# CAN_schematic.net
KiCad netlist of a schematic drawn in Altium Designer
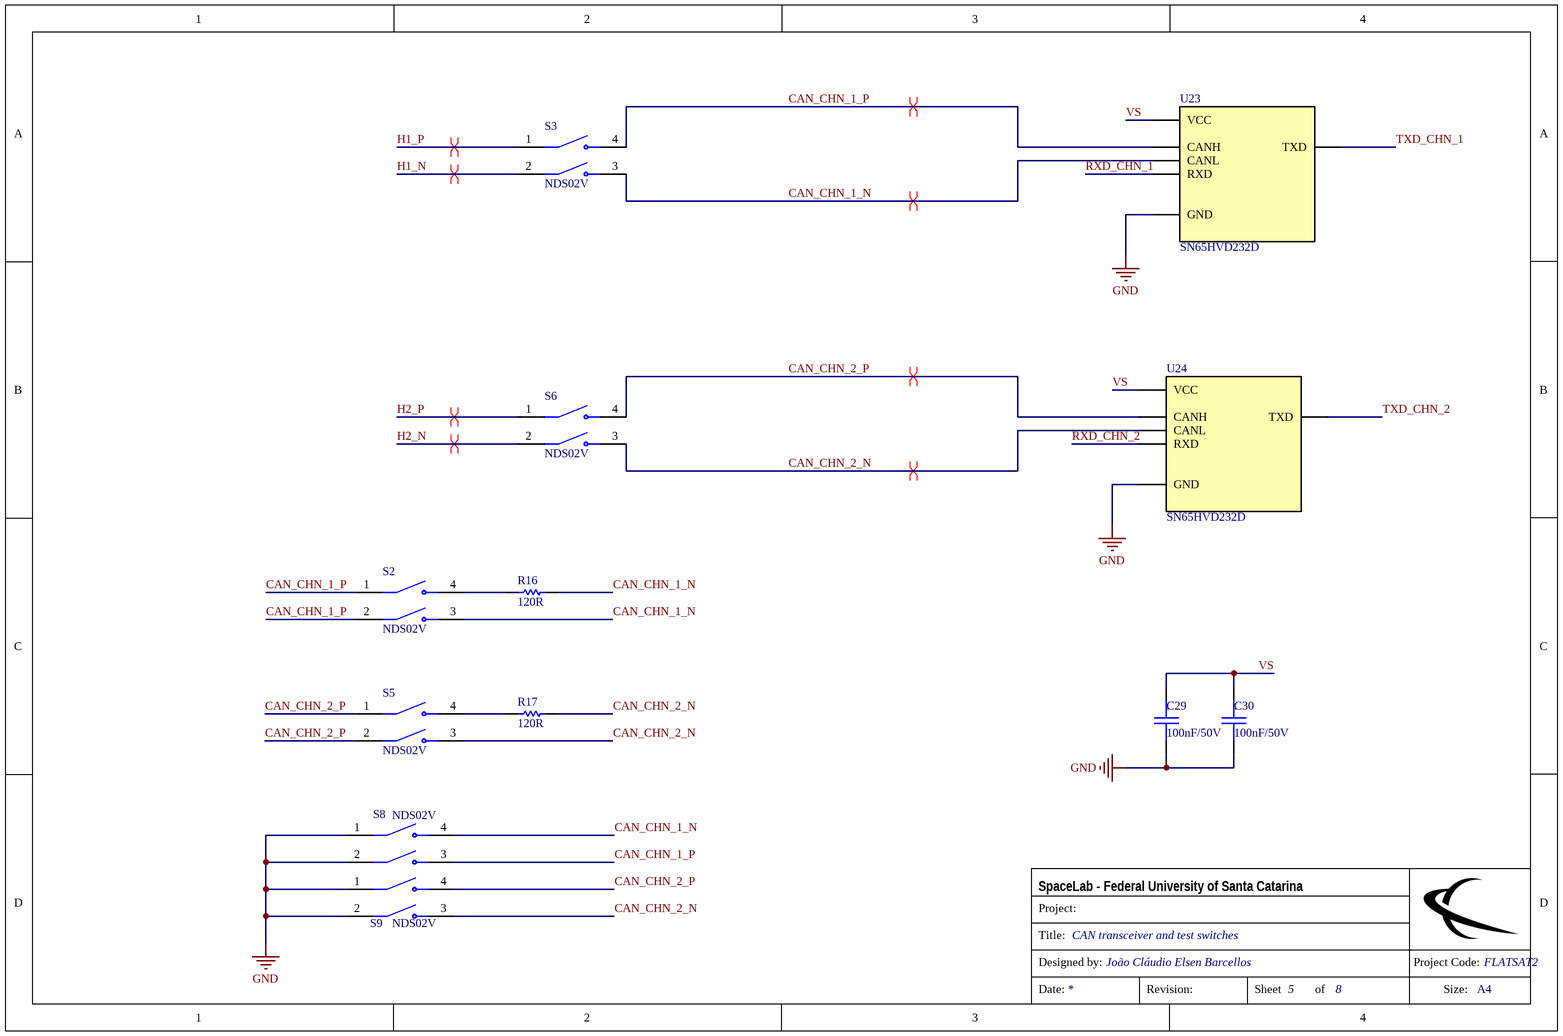
[diagram p0: CAN_schematic.SchDoc]

(export (version "E")
  (design (tool "Eeschema 10.0.6"))
  (components
    (comp (ref "C29")
      (value "100nF/50V")
      (footprint "CC0603")
      (description "CAP CER 100nF 50V 10% X7R 0603")
      (fields (field (name "MANUFACTURER PART NUMBER") "C0603C104K5RAC3121"))
      (libsource (lib "flatsat_platform_2") (part "Cap_Cer_X7R_100nF_50V_0603"))
    )
    (comp (ref "C30")
      (value "100nF/50V")
      (footprint "CC0603")
      (description "CAP CER 100nF 50V 10% X7R 0603")
      (fields (field (name "MANUFACTURER PART NUMBER") "C0603C104K5RAC3121"))
      (libsource (lib "flatsat_platform_2") (part "Cap_Cer_X7R_100nF_50V_0603"))
    )
    (comp (ref "R16")
      (value "120R")
      (footprint "0805")
      (description "RES 120R OHM 1/8W 1% 0805")
      (fields (field (name "MANUFACTURER PART NUMBER") "CRGCQ0805F120R"))
      (libsource (lib "flatsat_platform_2") (part "R120R_1%_1/4W_0805"))
    )
    (comp (ref "R17")
      (value "120R")
      (footprint "0805")
      (description "RES 120R OHM 1/8W 1% 0805")
      (fields (field (name "MANUFACTURER PART NUMBER") "CRGCQ0805F120R"))
      (libsource (lib "flatsat_platform_2") (part "R120R_1%_1/4W_0805"))
    )
    (comp (ref "S2")
      (value "NDS02V")
      (footprint "SamacSys:NDS02V")
      (description "Switch")
      (fields (field (name "MOUSER PART NUMBER") "642-NDS02V"))
      (libsource (lib "SamacSys") (part "NDS02V"))
    )
    (comp (ref "S3")
      (value "NDS02V")
      (footprint "SamacSys:NDS02V")
      (description "Switch")
      (fields (field (name "MOUSER PART NUMBER") "642-NDS02V"))
      (libsource (lib "SamacSys") (part "NDS02V"))
    )
    (comp (ref "S5")
      (value "NDS02V")
      (footprint "SamacSys:NDS02V")
      (description "Switch")
      (fields (field (name "MOUSER PART NUMBER") "642-NDS02V"))
      (libsource (lib "SamacSys") (part "NDS02V"))
    )
    (comp (ref "S6")
      (value "NDS02V")
      (footprint "SamacSys:NDS02V")
      (description "Switch")
      (fields (field (name "MOUSER PART NUMBER") "642-NDS02V"))
      (libsource (lib "SamacSys") (part "NDS02V"))
    )
    (comp (ref "S8")
      (value "NDS02V")
      (footprint "SamacSys:NDS02V")
      (description "Switch")
      (fields (field (name "MOUSER PART NUMBER") "642-NDS02V"))
      (libsource (lib "SamacSys") (part "NDS02V"))
    )
    (comp (ref "S9")
      (value "NDS02V")
      (footprint "SamacSys:NDS02V")
      (description "Switch")
      (fields (field (name "MOUSER PART NUMBER") "642-NDS02V"))
      (libsource (lib "SamacSys") (part "NDS02V"))
    )
    (comp (ref "U23")
      (value "SN65HVD232D")
      (footprint "SOIC127P599X175-8N")
      (description "3.3 V CAN Transceiver")
      (fields (field (name "MF") "Texas Instruments"))
      (libsource (lib "flatsat_platform_2") (part "SN65HVD232D"))
    )
    (comp (ref "U24")
      (value "SN65HVD232D")
      (footprint "SOIC127P599X175-8N")
      (description "3.3 V CAN Transceiver")
      (fields (field (name "MF") "Texas Instruments"))
      (libsource (lib "flatsat_platform_2") (part "SN65HVD232D"))
    )
  )
  (nets
    (net (code "1") (name "/CAN_CHN_1_N") (class "Default")
      (node (ref "R16") (pin "1") (pinfunction "1_1") (pintype "passive"))
      (node (ref "S2") (pin "3") (pinfunction "NO_1_3") (pintype "passive"))
      (node (ref "S3") (pin "3") (pinfunction "NO_1_3") (pintype "passive"))
      (node (ref "S8") (pin "4") (pinfunction "NO_2_4") (pintype "passive"))
      (node (ref "U23") (pin "6") (pinfunction "CANL_6") (pintype "power_in"))
    )
    (net (code "2") (name "/CAN_CHN_1_P") (class "Default")
      (node (ref "S2") (pin "1") (pinfunction "COM_1_1") (pintype "passive"))
      (node (ref "S2") (pin "2") (pinfunction "COM_2_2") (pintype "passive"))
      (node (ref "S3") (pin "4") (pinfunction "NO_2_4") (pintype "passive"))
      (node (ref "S8") (pin "3") (pinfunction "NO_1_3") (pintype "passive"))
      (node (ref "U23") (pin "7") (pinfunction "CANH_7") (pintype "power_in"))
    )
    (net (code "3") (name "/CAN_CHN_2_N") (class "Default")
      (node (ref "R17") (pin "1") (pinfunction "1_1") (pintype "passive"))
      (node (ref "S5") (pin "3") (pinfunction "NO_1_3") (pintype "passive"))
      (node (ref "S6") (pin "3") (pinfunction "NO_1_3") (pintype "passive"))
      (node (ref "S9") (pin "3") (pinfunction "NO_1_3") (pintype "passive"))
      (node (ref "U24") (pin "6") (pinfunction "CANL_6") (pintype "power_in"))
    )
    (net (code "4") (name "/CAN_CHN_2_P") (class "Default")
      (node (ref "S5") (pin "1") (pinfunction "COM_1_1") (pintype "passive"))
      (node (ref "S5") (pin "2") (pinfunction "COM_2_2") (pintype "passive"))
      (node (ref "S6") (pin "4") (pinfunction "NO_2_4") (pintype "passive"))
      (node (ref "S9") (pin "4") (pinfunction "NO_2_4") (pintype "passive"))
      (node (ref "U24") (pin "7") (pinfunction "CANH_7") (pintype "power_in"))
    )
    (net (code "5") (name "/H1_N") (class "Default")
      (node (ref "S3") (pin "2") (pinfunction "COM_2_2") (pintype "passive"))
    )
    (net (code "6") (name "/H1_P") (class "Default")
      (node (ref "S3") (pin "1") (pinfunction "COM_1_1") (pintype "passive"))
    )
    (net (code "7") (name "/H2_N") (class "Default")
      (node (ref "S6") (pin "2") (pinfunction "COM_2_2") (pintype "passive"))
    )
    (net (code "8") (name "/H2_P") (class "Default")
      (node (ref "S6") (pin "1") (pinfunction "COM_1_1") (pintype "passive"))
    )
    (net (code "9") (name "/RXD_CHN_1") (class "Default")
      (node (ref "U23") (pin "4") (pinfunction "RXD_4") (pintype "power_in"))
    )
    (net (code "10") (name "/RXD_CHN_2") (class "Default")
      (node (ref "U24") (pin "4") (pinfunction "RXD_4") (pintype "power_in"))
    )
    (net (code "11") (name "/TXD_CHN_1") (class "Default")
      (node (ref "U23") (pin "1") (pinfunction "TXD_1") (pintype "power_in"))
    )
    (net (code "12") (name "/TXD_CHN_2") (class "Default")
      (node (ref "U24") (pin "1") (pinfunction "TXD_1") (pintype "power_in"))
    )
    (net (code "13") (name "/VS") (class "Default")
      (node (ref "C29") (pin "1") (pinfunction "1_1") (pintype "passive"))
      (node (ref "C30") (pin "1") (pinfunction "1_1") (pintype "passive"))
      (node (ref "U23") (pin "3") (pinfunction "VCC_3") (pintype "power_in"))
      (node (ref "U24") (pin "3") (pinfunction "VCC_3") (pintype "power_in"))
    )
    (net (code "14") (name "GND") (class "Default")
      (node (ref "C29") (pin "2") (pinfunction "2_2") (pintype "passive"))
      (node (ref "C30") (pin "2") (pinfunction "2_2") (pintype "passive"))
      (node (ref "S8") (pin "1") (pinfunction "COM_1_1") (pintype "passive"))
      (node (ref "S8") (pin "2") (pinfunction "COM_2_2") (pintype "passive"))
      (node (ref "S9") (pin "1") (pinfunction "COM_1_1") (pintype "passive"))
      (node (ref "S9") (pin "2") (pinfunction "COM_2_2") (pintype "passive"))
      (node (ref "U23") (pin "2") (pinfunction "GND_2") (pintype "power_in"))
      (node (ref "U24") (pin "2") (pinfunction "GND_2") (pintype "power_in"))
    )
    (net (code "15") (name "Net-(S2-NO_2)") (class "Default")
      (node (ref "R16") (pin "2") (pinfunction "2_2") (pintype "passive"))
      (node (ref "S2") (pin "4") (pinfunction "NO_2_4") (pintype "passive"))
    )
    (net (code "16") (name "Net-(S5-NO_2)") (class "Default")
      (node (ref "R17") (pin "2") (pinfunction "2_2") (pintype "passive"))
      (node (ref "S5") (pin "4") (pinfunction "NO_2_4") (pintype "passive"))
    )
  )
)
